# System_Clocks.net
KiCad netlist of a schematic drawn in Altium Designer
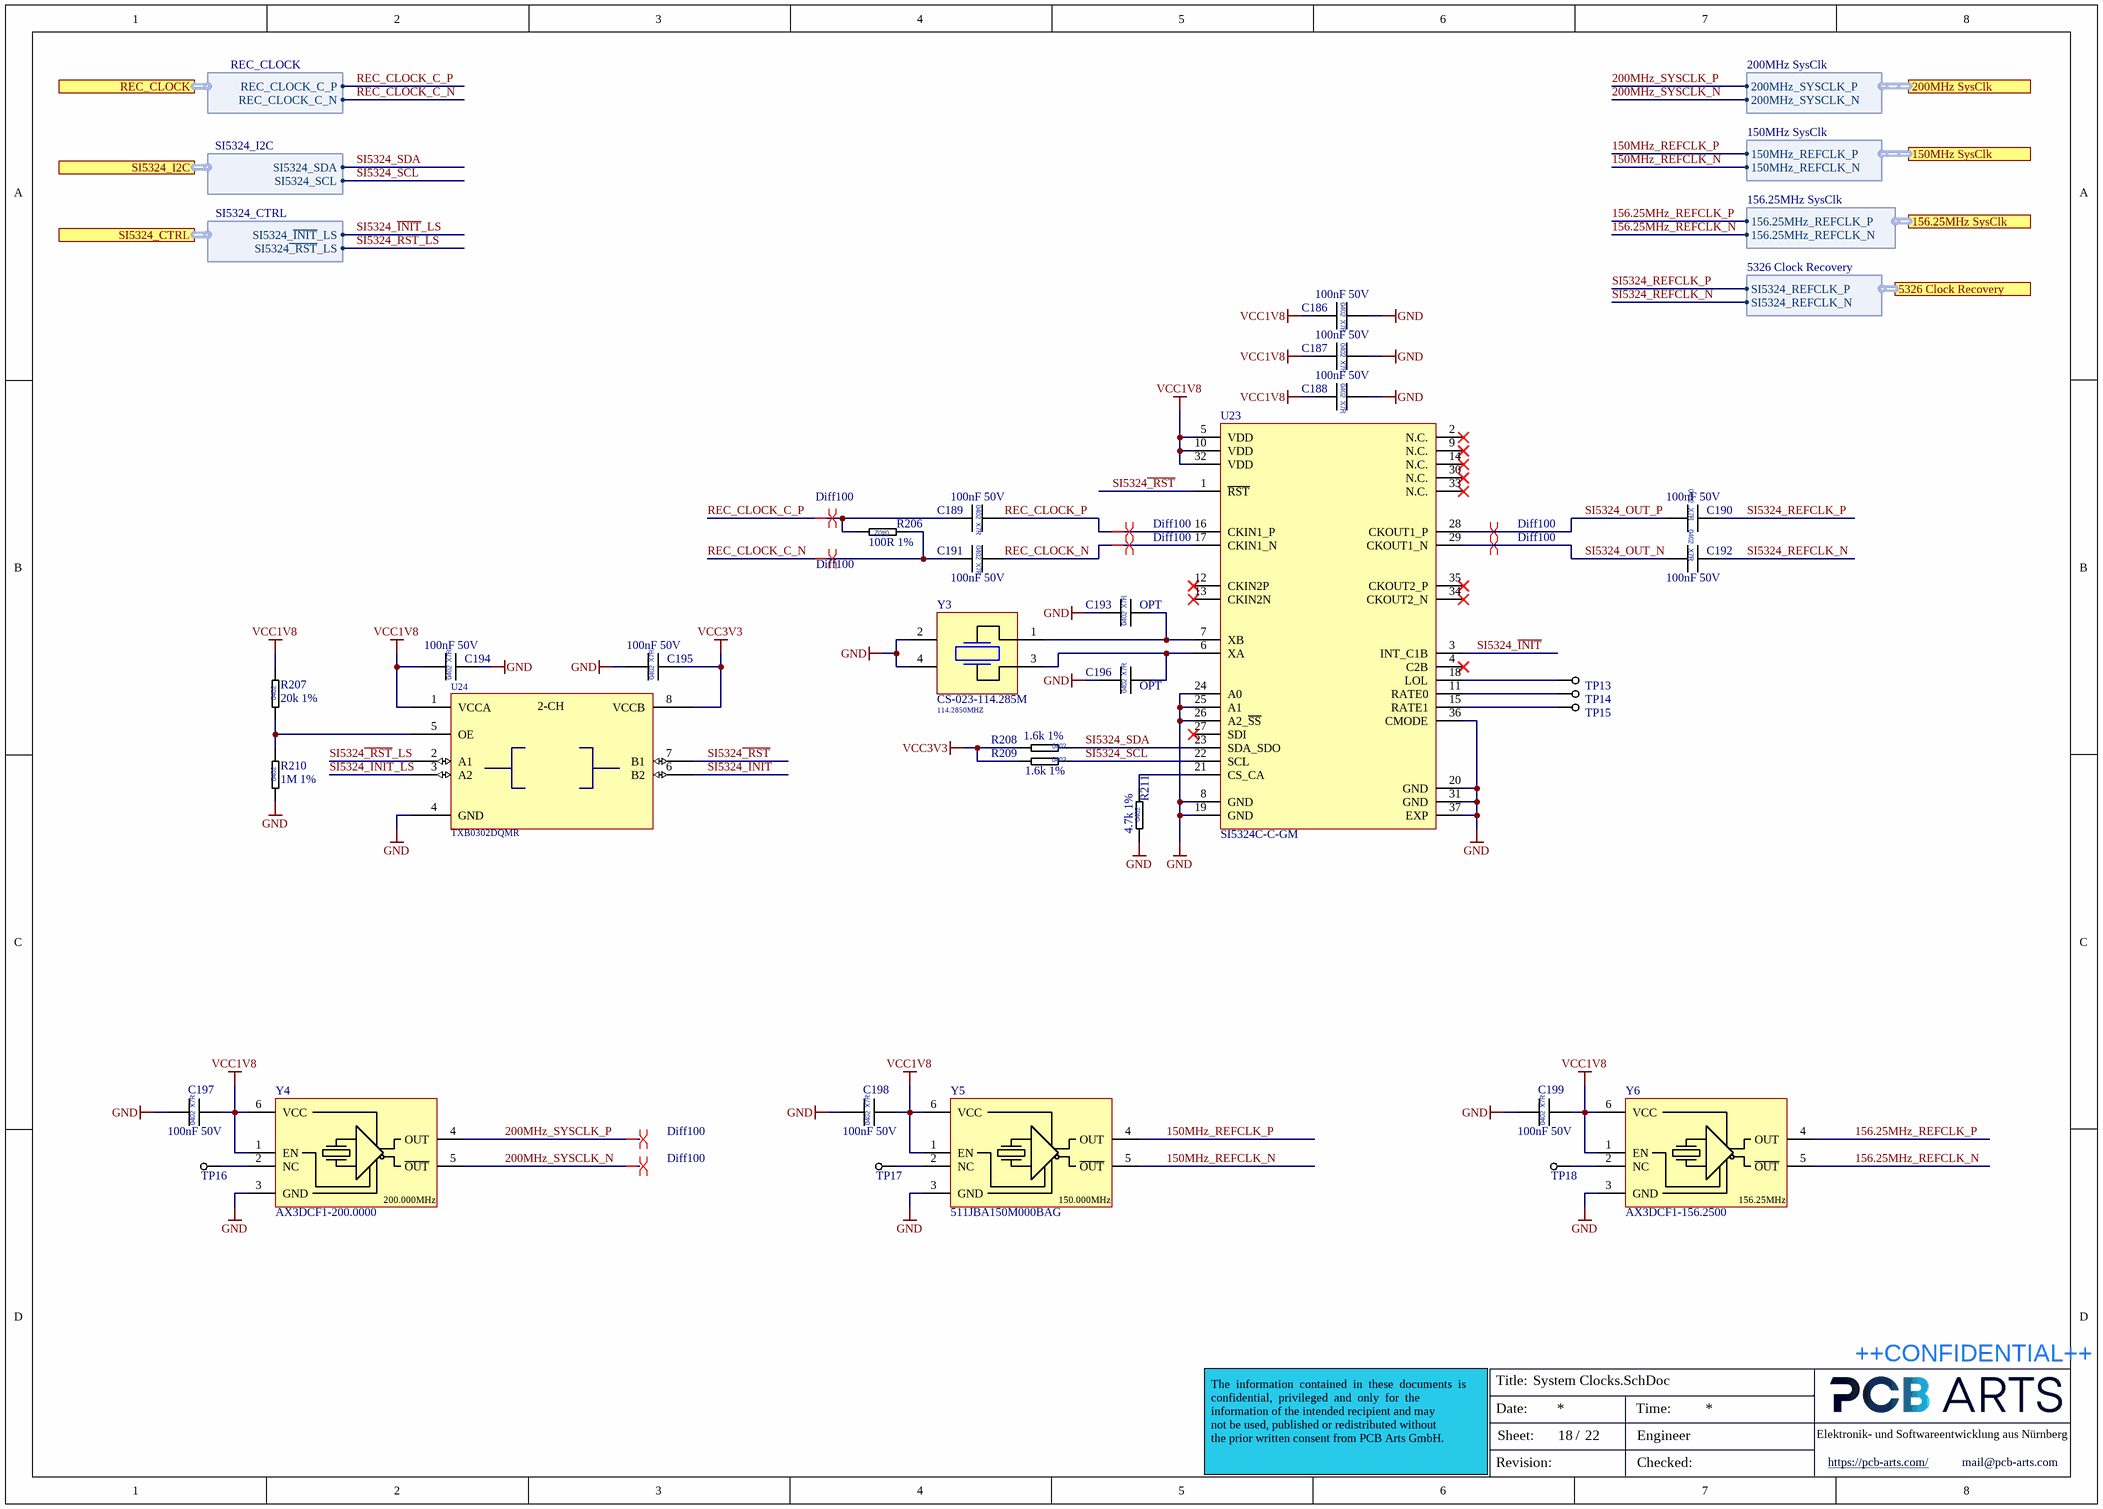
[diagram p0: System Clocks.SchDoc]

(export (version "E")
  (design (tool "Eeschema 10.0.6"))
  (components
    (comp (ref "C186")
      (value "100nF 50V")
      (footprint "Cap:CAP_0402_L")
      (description "Multilayer Ceramic Capacitors MLCC - SMD/SMT 0402 50VDC")
      (libsource (lib "Cap") (part "CAP_0402_100nF_50V"))
    )
    (comp (ref "C187")
      (value "100nF 50V")
      (footprint "Cap:CAP_0402_L")
      (description "Multilayer Ceramic Capacitors MLCC - SMD/SMT 0402 50VDC")
      (libsource (lib "Cap") (part "CAP_0402_100nF_50V"))
    )
    (comp (ref "C188")
      (value "100nF 50V")
      (footprint "Cap:CAP_0402_L")
      (description "Multilayer Ceramic Capacitors MLCC - SMD/SMT 0402 50VDC")
      (libsource (lib "Cap") (part "CAP_0402_100nF_50V"))
    )
    (comp (ref "C189")
      (value "100nF 50V")
      (footprint "Cap:CAP_0402_L")
      (description "Multilayer Ceramic Capacitors MLCC - SMD/SMT 0402 50VDC")
      (libsource (lib "Cap") (part "CAP_0402_100nF_50V"))
    )
    (comp (ref "C190")
      (value "100nF 50V")
      (footprint "Cap:CAP_0402_L")
      (description "Multilayer Ceramic Capacitors MLCC - SMD/SMT 0402 50VDC")
      (libsource (lib "") (part "CAP_0402_100nF_50V_1"))
    )
    (comp (ref "C191")
      (value "100nF 50V")
      (footprint "Cap:CAP_0402_L")
      (description "Multilayer Ceramic Capacitors MLCC - SMD/SMT 0402 50VDC")
      (libsource (lib "Cap") (part "CAP_0402_100nF_50V"))
    )
    (comp (ref "C192")
      (value "100nF 50V")
      (footprint "Cap:CAP_0402_L")
      (description "Multilayer Ceramic Capacitors MLCC - SMD/SMT 0402 50VDC")
      (libsource (lib "") (part "CAP_0402_100nF_50V_1"))
    )
    (comp (ref "C193")
      (value "OPT")
      (footprint "Cap:CAP_0402_L")
      (description "Multilayer Ceramic Capacitors MLCC - SMD/SMT 0402 Optional Placeholder")
      (libsource (lib "Cap") (part "CAP_0402_OPT"))
    )
    (comp (ref "C194")
      (value "100nF 50V")
      (footprint "Cap:CAP_0402_L")
      (description "Multilayer Ceramic Capacitors MLCC - SMD/SMT 0402 50VDC")
      (libsource (lib "") (part "CAP_0402_100nF_50V_1"))
    )
    (comp (ref "C195")
      (value "100nF 50V")
      (footprint "Cap:CAP_0402_L")
      (description "Multilayer Ceramic Capacitors MLCC - SMD/SMT 0402 50VDC")
      (libsource (lib "") (part "CAP_0402_100nF_50V_1"))
    )
    (comp (ref "C196")
      (value "OPT")
      (footprint "Cap:CAP_0402_L")
      (description "Multilayer Ceramic Capacitors MLCC - SMD/SMT 0402 Optional Placeholder")
      (libsource (lib "Cap") (part "CAP_0402_OPT"))
    )
    (comp (ref "C197")
      (value "100nF 50V")
      (footprint "Cap:CAP_0402_L")
      (description "Multilayer Ceramic Capacitors MLCC - SMD/SMT 0402 50VDC")
      (libsource (lib "") (part "CAP_0402_100nF_50V_1"))
    )
    (comp (ref "C198")
      (value "100nF 50V")
      (footprint "Cap:CAP_0402_L")
      (description "Multilayer Ceramic Capacitors MLCC - SMD/SMT 0402 50VDC")
      (libsource (lib "") (part "CAP_0402_100nF_50V_1"))
    )
    (comp (ref "C199")
      (value "100nF 50V")
      (footprint "Cap:CAP_0402_L")
      (description "Multilayer Ceramic Capacitors MLCC - SMD/SMT 0402 50VDC")
      (libsource (lib "") (part "CAP_0402_100nF_50V_1"))
    )
    (comp (ref "R206")
      (value "100R 1%")
      (footprint "Res:RES_0402_L")
      (description "Thick Film Resistors - SMD 100Ohm 1%")
      (libsource (lib "Res") (part "RES_0402_100R_1%"))
    )
    (comp (ref "R207")
      (value "20k 1%")
      (footprint "Res:RES_0402_L")
      (description "Thick Film Resistors - SMD 20kOhm 1%")
      (libsource (lib "Res") (part "RES_0402_20k_1%"))
    )
    (comp (ref "R208")
      (value "1.6k 1%")
      (footprint "Res:RES_0402_L")
      (description "Thick Film Resistors - SMD 1.6kOhm 1%")
      (libsource (lib "Res") (part "RES_0402_1.6k_1%"))
    )
    (comp (ref "R209")
      (value "1.6k 1%")
      (footprint "Res:RES_0402_L")
      (description "Thick Film Resistors - SMD 1.6kOhm 1%")
      (libsource (lib "Res") (part "RES_0402_1.6k_1%"))
    )
    (comp (ref "R210")
      (value "1M 1%")
      (footprint "Res:RES_0402_L")
      (description "Thick Film Resistors - SMD 1MOhm 1%")
      (libsource (lib "Res") (part "RES_0402_1M_1%"))
    )
    (comp (ref "R211")
      (value "4.7k 1%")
      (footprint "Res:RES_0402_L")
      (description "Thick Film Resistors - SMD 4.7kOhm 1%")
      (libsource (lib "Res") (part "RES_0402_4.7k_1%"))
    )
    (comp (ref "TP13")
      (value "Testpoint")
      (footprint "Electro_mech:Testpoint 0.8mm")
      (description "Testpoint 0.8mm")
      (libsource (lib "Electro_Mech") (part "Testpoint 0.8mm"))
    )
    (comp (ref "TP14")
      (value "Testpoint")
      (footprint "Electro_mech:Testpoint 0.8mm")
      (description "Testpoint 0.8mm")
      (libsource (lib "Electro_Mech") (part "Testpoint 0.8mm"))
    )
    (comp (ref "TP15")
      (value "Testpoint")
      (footprint "Electro_mech:Testpoint 0.8mm")
      (description "Testpoint 0.8mm")
      (libsource (lib "Electro_Mech") (part "Testpoint 0.8mm"))
    )
    (comp (ref "TP16")
      (value "Testpoint")
      (footprint "Electro_mech:Testpoint 0.8mm")
      (description "Testpoint 0.8mm")
      (libsource (lib "Electro_Mech") (part "Testpoint 0.8mm"))
    )
    (comp (ref "TP17")
      (value "Testpoint")
      (footprint "Electro_mech:Testpoint 0.8mm")
      (description "Testpoint 0.8mm")
      (libsource (lib "Electro_Mech") (part "Testpoint 0.8mm"))
    )
    (comp (ref "TP18")
      (value "Testpoint")
      (footprint "Electro_mech:Testpoint 0.8mm")
      (description "Testpoint 0.8mm")
      (libsource (lib "Electro_Mech") (part "Testpoint 0.8mm"))
    )
    (comp (ref "U23")
      (value "SI5324C-C-GM")
      (footprint "Timer:QFN50P600X600X85-37N")
      (description "PRECISION CLOCK MULTIPLIER/ JITTER ATTENUATOR")
      (libsource (lib "Timer") (part "SI5324C-C-GM_PRECISION CLOCK MULTIPLIER/ JITTER ATTENUATOR"))
    )
    (comp (ref "U24")
      (value "TXB0302DQMR")
      (footprint "Digital:SON40P120X40-8N")
      (description "Translation - Voltage Levels 2B Bidir Vltg-Level Translator")
      (libsource (lib "Digital") (part "TXB0302DQMR_Translation - Voltage Levels 2B Bidir Vltg-Level Translator"))
    )
    (comp (ref "Y3")
      (value "CS-023-114.285M")
      (footprint "Timer:S3D - Shenzhen SCTF Elec")
      (description "3.2 x 2.5 x 0.8 mm SMD Crystal")
      (fields (field (name "FREQUENCY") "114.2850MHZ"))
      (libsource (lib "Timer") (part "Quarz 114.2850MHz ESR 80R 18pF"))
    )
    (comp (ref "Y4")
      (value "AX3DCF1-200.0000")
      (footprint "Timer:Abracon AX3")
      (description "200MHz Clock Oscillator, 1V8, LVDS")
      (libsource (lib "Timer") (part "AX3DCF1-200.0000_200MHz Clock Oscillator, 1V8, LVDS"))
    )
    (comp (ref "Y5")
      (value "511JBA150M000BAG")
      (footprint "Timer:Abracon AX3")
      (description "150MHz Clock Oscillator, 1V8, LVDS")
      (libsource (lib "Timer") (part "511JBA150M000BAG_150MHz Clock Oscillator, 1V8, LVDS"))
    )
    (comp (ref "Y6")
      (value "AX3DCF1-156.2500")
      (footprint "Timer:Abracon AX3")
      (description "156.25MHz Clock Oscillator, 1V8, LVDS")
      (libsource (lib "Timer") (part "AX3DCF1-156.2500_156.25MHz Clock Oscillator, 1V8, LVDS"))
    )
  )
  (nets
    (net (code "11") (name "/150MHz_REFCLK_N") (class "Default")
      (node (ref "Y5") (pin "5") (pinfunction "~{OUT}_5") (pintype "passive"))
    )
    (net (code "12") (name "/150MHz_REFCLK_P") (class "Default")
      (node (ref "Y5") (pin "4") (pinfunction "OUT_4") (pintype "passive"))
    )
    (net (code "13") (name "/156.25MHz_REFCLK_N") (class "Default")
      (node (ref "Y6") (pin "5") (pinfunction "~{OUT}_5") (pintype "passive"))
    )
    (net (code "14") (name "/156.25MHz_REFCLK_P") (class "Default")
      (node (ref "Y6") (pin "4") (pinfunction "OUT_4") (pintype "passive"))
    )
    (net (code "15") (name "/200MHz_SYSCLK_N") (class "Default")
      (node (ref "Y4") (pin "5") (pinfunction "~{OUT}_5") (pintype "passive"))
    )
    (net (code "16") (name "/200MHz_SYSCLK_P") (class "Default")
      (node (ref "Y4") (pin "4") (pinfunction "OUT_4") (pintype "passive"))
    )
    (net (code "17") (name "/REC_CLOCK_C_N") (class "Default")
      (node (ref "C191") (pin "2") (pinfunction "2_2") (pintype "passive"))
      (node (ref "R206") (pin "1") (pinfunction "1_1") (pintype "passive"))
    )
    (net (code "18") (name "/REC_CLOCK_C_P") (class "Default")
      (node (ref "C189") (pin "2") (pinfunction "2_2") (pintype "passive"))
      (node (ref "R206") (pin "2") (pinfunction "2_2") (pintype "passive"))
    )
    (net (code "19") (name "/REC_CLOCK_N") (class "Default")
      (node (ref "C191") (pin "1") (pinfunction "1_1") (pintype "passive"))
      (node (ref "U23") (pin "17") (pinfunction "CKIN1_N_17") (pintype "passive"))
    )
    (net (code "20") (name "/REC_CLOCK_P") (class "Default")
      (node (ref "C189") (pin "1") (pinfunction "1_1") (pintype "passive"))
      (node (ref "U23") (pin "16") (pinfunction "CKIN1_P_16") (pintype "passive"))
    )
    (net (code "21") (name "/SI5324_OUT_N") (class "Default")
      (node (ref "C192") (pin "1") (pinfunction "1_1") (pintype "passive"))
      (node (ref "U23") (pin "29") (pinfunction "CKOUT1_N_29") (pintype "passive"))
    )
    (net (code "22") (name "/SI5324_OUT_P") (class "Default")
      (node (ref "C190") (pin "1") (pinfunction "1_1") (pintype "passive"))
      (node (ref "U23") (pin "28") (pinfunction "CKOUT1_P_28") (pintype "passive"))
    )
    (net (code "23") (name "/SI5324_REFCLK_N") (class "Default")
      (node (ref "C192") (pin "2") (pinfunction "2_2") (pintype "passive"))
    )
    (net (code "24") (name "/SI5324_REFCLK_P") (class "Default")
      (node (ref "C190") (pin "2") (pinfunction "2_2") (pintype "passive"))
    )
    (net (code "25") (name "/SI5324_SCL") (class "Default")
      (node (ref "R209") (pin "1") (pinfunction "1_1") (pintype "passive"))
      (node (ref "U23") (pin "22") (pinfunction "SCL_22") (pintype "passive"))
    )
    (net (code "26") (name "/SI5324_SDA") (class "Default")
      (node (ref "R208") (pin "1") (pinfunction "1_1") (pintype "passive"))
      (node (ref "U23") (pin "23") (pinfunction "SDA_SDO_23") (pintype "passive"))
    )
    (net (code "27") (name "/SI5324_~{INIT}") (class "Default")
      (node (ref "U23") (pin "3") (pinfunction "INT_C1B_3") (pintype "passive"))
      (node (ref "U24") (pin "6") (pinfunction "B2_6") (pintype "bidirectional"))
    )
    (net (code "28") (name "/SI5324_~{INIT}_LS") (class "Default")
      (node (ref "U24") (pin "3") (pinfunction "A2_3") (pintype "bidirectional"))
    )
    (net (code "29") (name "/SI5324~{_RST}") (class "Default")
      (node (ref "U23") (pin "1") (pinfunction "~{RST}_1") (pintype "passive"))
      (node (ref "U24") (pin "7") (pinfunction "B1_7") (pintype "bidirectional"))
    )
    (net (code "30") (name "/SI5324~{_RST}_LS") (class "Default")
      (node (ref "U24") (pin "2") (pinfunction "A1_2") (pintype "bidirectional"))
    )
    (net (code "38") (name "GND") (class "Default")
      (node (ref "C186") (pin "1") (pinfunction "1_1") (pintype "passive"))
      (node (ref "C187") (pin "1") (pinfunction "1_1") (pintype "passive"))
      (node (ref "C188") (pin "1") (pinfunction "1_1") (pintype "passive"))
      (node (ref "C193") (pin "1") (pinfunction "1_1") (pintype "passive"))
      (node (ref "C194") (pin "2") (pinfunction "2_2") (pintype "passive"))
      (node (ref "C195") (pin "1") (pinfunction "1_1") (pintype "passive"))
      (node (ref "C196") (pin "1") (pinfunction "1_1") (pintype "passive"))
      (node (ref "C197") (pin "1") (pinfunction "1_1") (pintype "passive"))
      (node (ref "C198") (pin "1") (pinfunction "1_1") (pintype "passive"))
      (node (ref "C199") (pin "1") (pinfunction "1_1") (pintype "passive"))
      (node (ref "R210") (pin "1") (pinfunction "1_1") (pintype "passive"))
      (node (ref "R211") (pin "1") (pinfunction "1_1") (pintype "passive"))
      (node (ref "U23") (pin "19") (pinfunction "GND_19") (pintype "passive"))
      (node (ref "U23") (pin "20") (pinfunction "GND_20") (pintype "passive"))
      (node (ref "U23") (pin "24") (pinfunction "A0_24") (pintype "passive"))
      (node (ref "U23") (pin "25") (pinfunction "A1_25") (pintype "passive"))
      (node (ref "U23") (pin "26") (pinfunction "A2_~{SS}_26") (pintype "passive"))
      (node (ref "U23") (pin "31") (pinfunction "GND_31") (pintype "passive"))
      (node (ref "U23") (pin "36") (pinfunction "CMODE_36") (pintype "passive"))
      (node (ref "U23") (pin "37") (pinfunction "EXP_37") (pintype "passive"))
      (node (ref "U23") (pin "8") (pinfunction "GND_8") (pintype "passive"))
      (node (ref "U24") (pin "4") (pinfunction "GND_4") (pintype "power_in"))
      (node (ref "Y3") (pin "2") (pinfunction "2_2") (pintype "passive"))
      (node (ref "Y3") (pin "4") (pinfunction "4_4") (pintype "passive"))
      (node (ref "Y4") (pin "3") (pinfunction "GND_3") (pintype "passive"))
      (node (ref "Y5") (pin "3") (pinfunction "GND_3") (pintype "passive"))
      (node (ref "Y6") (pin "3") (pinfunction "GND_3") (pintype "passive"))
    )
    (net (code "39") (name "Net-(TP13-GND)") (class "Default")
      (node (ref "TP13") (pin "1") (pinfunction "GND_1") (pintype "passive"))
      (node (ref "U23") (pin "18") (pinfunction "LOL_18") (pintype "passive"))
    )
    (net (code "40") (name "Net-(TP14-GND)") (class "Default")
      (node (ref "TP14") (pin "1") (pinfunction "GND_1") (pintype "passive"))
      (node (ref "U23") (pin "11") (pinfunction "RATE0_11") (pintype "passive"))
    )
    (net (code "41") (name "Net-(TP15-GND)") (class "Default")
      (node (ref "TP15") (pin "1") (pinfunction "GND_1") (pintype "passive"))
      (node (ref "U23") (pin "15") (pinfunction "RATE1_15") (pintype "passive"))
    )
    (net (code "42") (name "Net-(TP16-GND)") (class "Default")
      (node (ref "TP16") (pin "1") (pinfunction "GND_1") (pintype "passive"))
      (node (ref "Y4") (pin "2") (pinfunction "NC_2") (pintype "passive"))
    )
    (net (code "43") (name "Net-(TP17-GND)") (class "Default")
      (node (ref "TP17") (pin "1") (pinfunction "GND_1") (pintype "passive"))
      (node (ref "Y5") (pin "2") (pinfunction "NC_2") (pintype "passive"))
    )
    (net (code "44") (name "Net-(TP18-GND)") (class "Default")
      (node (ref "TP18") (pin "1") (pinfunction "GND_1") (pintype "passive"))
      (node (ref "Y6") (pin "2") (pinfunction "NC_2") (pintype "passive"))
    )
    (net (code "45") (name "Net-(U23-CS_CA)") (class "Default")
      (node (ref "R211") (pin "2") (pinfunction "2_2") (pintype "passive"))
      (node (ref "U23") (pin "21") (pinfunction "CS_CA_21") (pintype "passive"))
    )
    (net (code "46") (name "Net-(U23-XA)") (class "Default")
      (node (ref "C196") (pin "2") (pinfunction "2_2") (pintype "passive"))
      (node (ref "U23") (pin "6") (pinfunction "XA_6") (pintype "passive"))
      (node (ref "Y3") (pin "3") (pinfunction "3_3") (pintype "passive"))
    )
    (net (code "47") (name "Net-(U23-XB)") (class "Default")
      (node (ref "C193") (pin "2") (pinfunction "2_2") (pintype "passive"))
      (node (ref "U23") (pin "7") (pinfunction "XB_7") (pintype "passive"))
      (node (ref "Y3") (pin "1") (pinfunction "1_1") (pintype "passive"))
    )
    (net (code "48") (name "Net-(U24-OE)") (class "Default")
      (node (ref "R207") (pin "1") (pinfunction "1_1") (pintype "passive"))
      (node (ref "R210") (pin "2") (pinfunction "2_2") (pintype "passive"))
      (node (ref "U24") (pin "5") (pinfunction "OE_5") (pintype "power_in"))
    )
    (net (code "49") (name "VCC1V8") (class "Default")
      (node (ref "C186") (pin "2") (pinfunction "2_2") (pintype "passive"))
      (node (ref "C187") (pin "2") (pinfunction "2_2") (pintype "passive"))
      (node (ref "C188") (pin "2") (pinfunction "2_2") (pintype "passive"))
      (node (ref "C194") (pin "1") (pinfunction "1_1") (pintype "passive"))
      (node (ref "C197") (pin "2") (pinfunction "2_2") (pintype "passive"))
      (node (ref "C198") (pin "2") (pinfunction "2_2") (pintype "passive"))
      (node (ref "C199") (pin "2") (pinfunction "2_2") (pintype "passive"))
      (node (ref "R207") (pin "2") (pinfunction "2_2") (pintype "passive"))
      (node (ref "U23") (pin "10") (pinfunction "VDD_10") (pintype "passive"))
      (node (ref "U23") (pin "32") (pinfunction "VDD_32") (pintype "passive"))
      (node (ref "U23") (pin "5") (pinfunction "VDD_5") (pintype "passive"))
      (node (ref "U24") (pin "1") (pinfunction "VCCA_1") (pintype "power_in"))
      (node (ref "Y4") (pin "1") (pinfunction "EN_1") (pintype "passive"))
      (node (ref "Y4") (pin "6") (pinfunction "VCC_6") (pintype "passive"))
      (node (ref "Y5") (pin "1") (pinfunction "EN_1") (pintype "passive"))
      (node (ref "Y5") (pin "6") (pinfunction "VCC_6") (pintype "passive"))
      (node (ref "Y6") (pin "1") (pinfunction "EN_1") (pintype "passive"))
      (node (ref "Y6") (pin "6") (pinfunction "VCC_6") (pintype "passive"))
    )
    (net (code "50") (name "VCC3V3") (class "Default")
      (node (ref "C195") (pin "2") (pinfunction "2_2") (pintype "passive"))
      (node (ref "R208") (pin "2") (pinfunction "2_2") (pintype "passive"))
      (node (ref "R209") (pin "2") (pinfunction "2_2") (pintype "passive"))
      (node (ref "U24") (pin "8") (pinfunction "VCCB_8") (pintype "power_in"))
    )
    (net (code "51") (name "unconnected-(U23-C2B-Pad4)") (class "Default")
      (node (ref "U23") (pin "4") (pinfunction "C2B_4") (pintype "passive+no_connect"))
    )
    (net (code "52") (name "unconnected-(U23-CKIN2N-Pad13)") (class "Default")
      (node (ref "U23") (pin "13") (pinfunction "CKIN2N_13") (pintype "passive+no_connect"))
    )
    (net (code "53") (name "unconnected-(U23-CKIN2P-Pad12)") (class "Default")
      (node (ref "U23") (pin "12") (pinfunction "CKIN2P_12") (pintype "passive+no_connect"))
    )
    (net (code "54") (name "unconnected-(U23-CKOUT2_N-Pad34)") (class "Default")
      (node (ref "U23") (pin "34") (pinfunction "CKOUT2_N_34") (pintype "passive+no_connect"))
    )
    (net (code "55") (name "unconnected-(U23-CKOUT2_P-Pad35)") (class "Default")
      (node (ref "U23") (pin "35") (pinfunction "CKOUT2_P_35") (pintype "passive+no_connect"))
    )
    (net (code "56") (name "unconnected-(U23-N.C.-Pad2)") (class "Default")
      (node (ref "U23") (pin "2") (pinfunction "N.C._2") (pintype "passive+no_connect"))
    )
    (net (code "57") (name "unconnected-(U23-N.C.-Pad9)") (class "Default")
      (node (ref "U23") (pin "9") (pinfunction "N.C._9") (pintype "passive+no_connect"))
    )
    (net (code "58") (name "unconnected-(U23-N.C.-Pad14)") (class "Default")
      (node (ref "U23") (pin "14") (pinfunction "N.C._14") (pintype "passive+no_connect"))
    )
    (net (code "59") (name "unconnected-(U23-N.C.-Pad30)") (class "Default")
      (node (ref "U23") (pin "30") (pinfunction "N.C._30") (pintype "passive+no_connect"))
    )
    (net (code "60") (name "unconnected-(U23-N.C.-Pad33)") (class "Default")
      (node (ref "U23") (pin "33") (pinfunction "N.C._33") (pintype "passive+no_connect"))
    )
    (net (code "61") (name "unconnected-(U23-SDI-Pad27)") (class "Default")
      (node (ref "U23") (pin "27") (pinfunction "SDI_27") (pintype "passive+no_connect"))
    )
  )
)
